# SCK_DATA_BOARD_2_0_REV_03.net
KiCad netlist of a schematic drawn in EAGLE
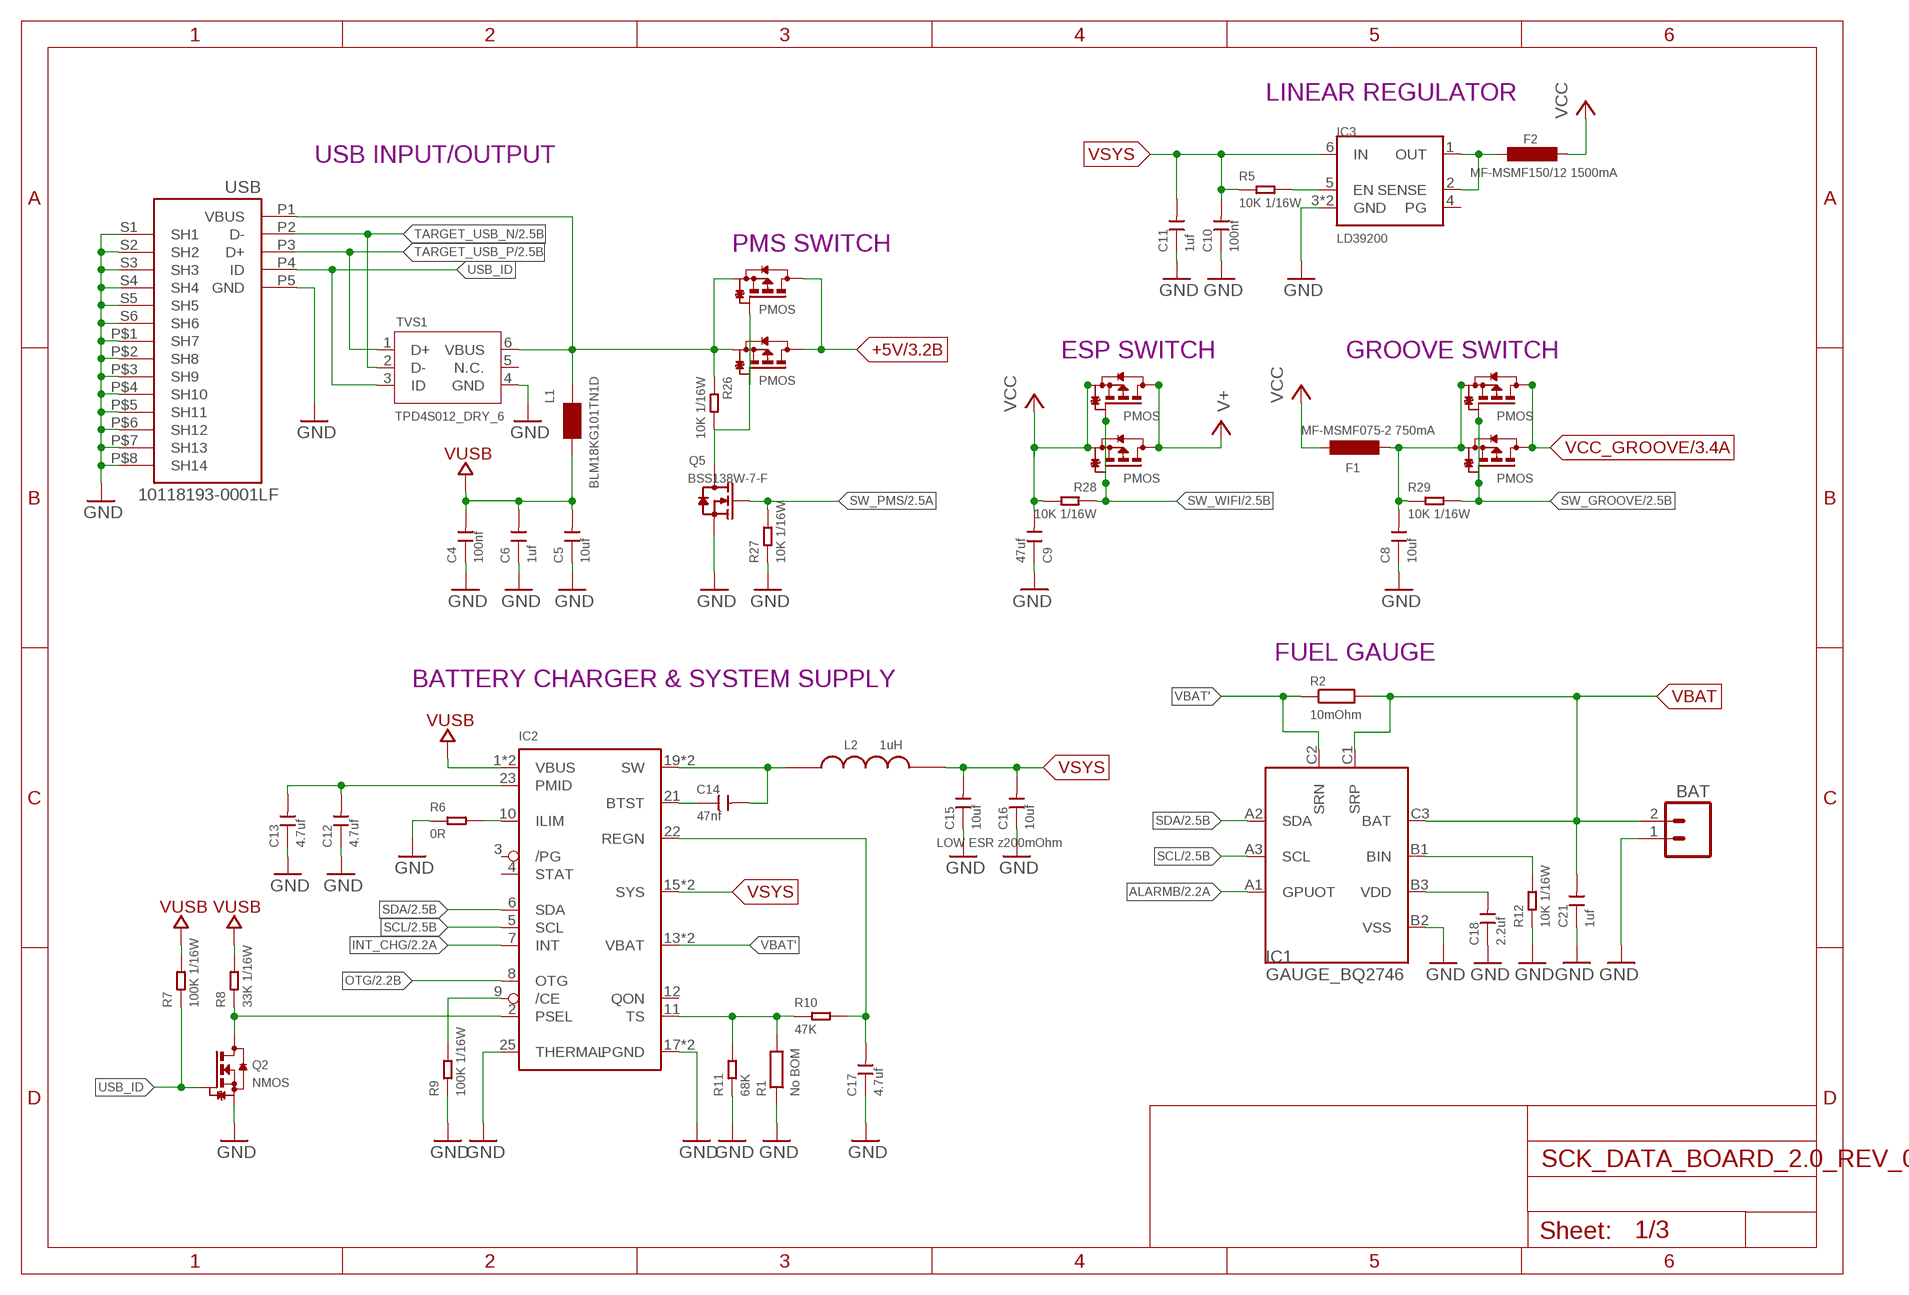
[diagram p0: schematic, sheet 1]
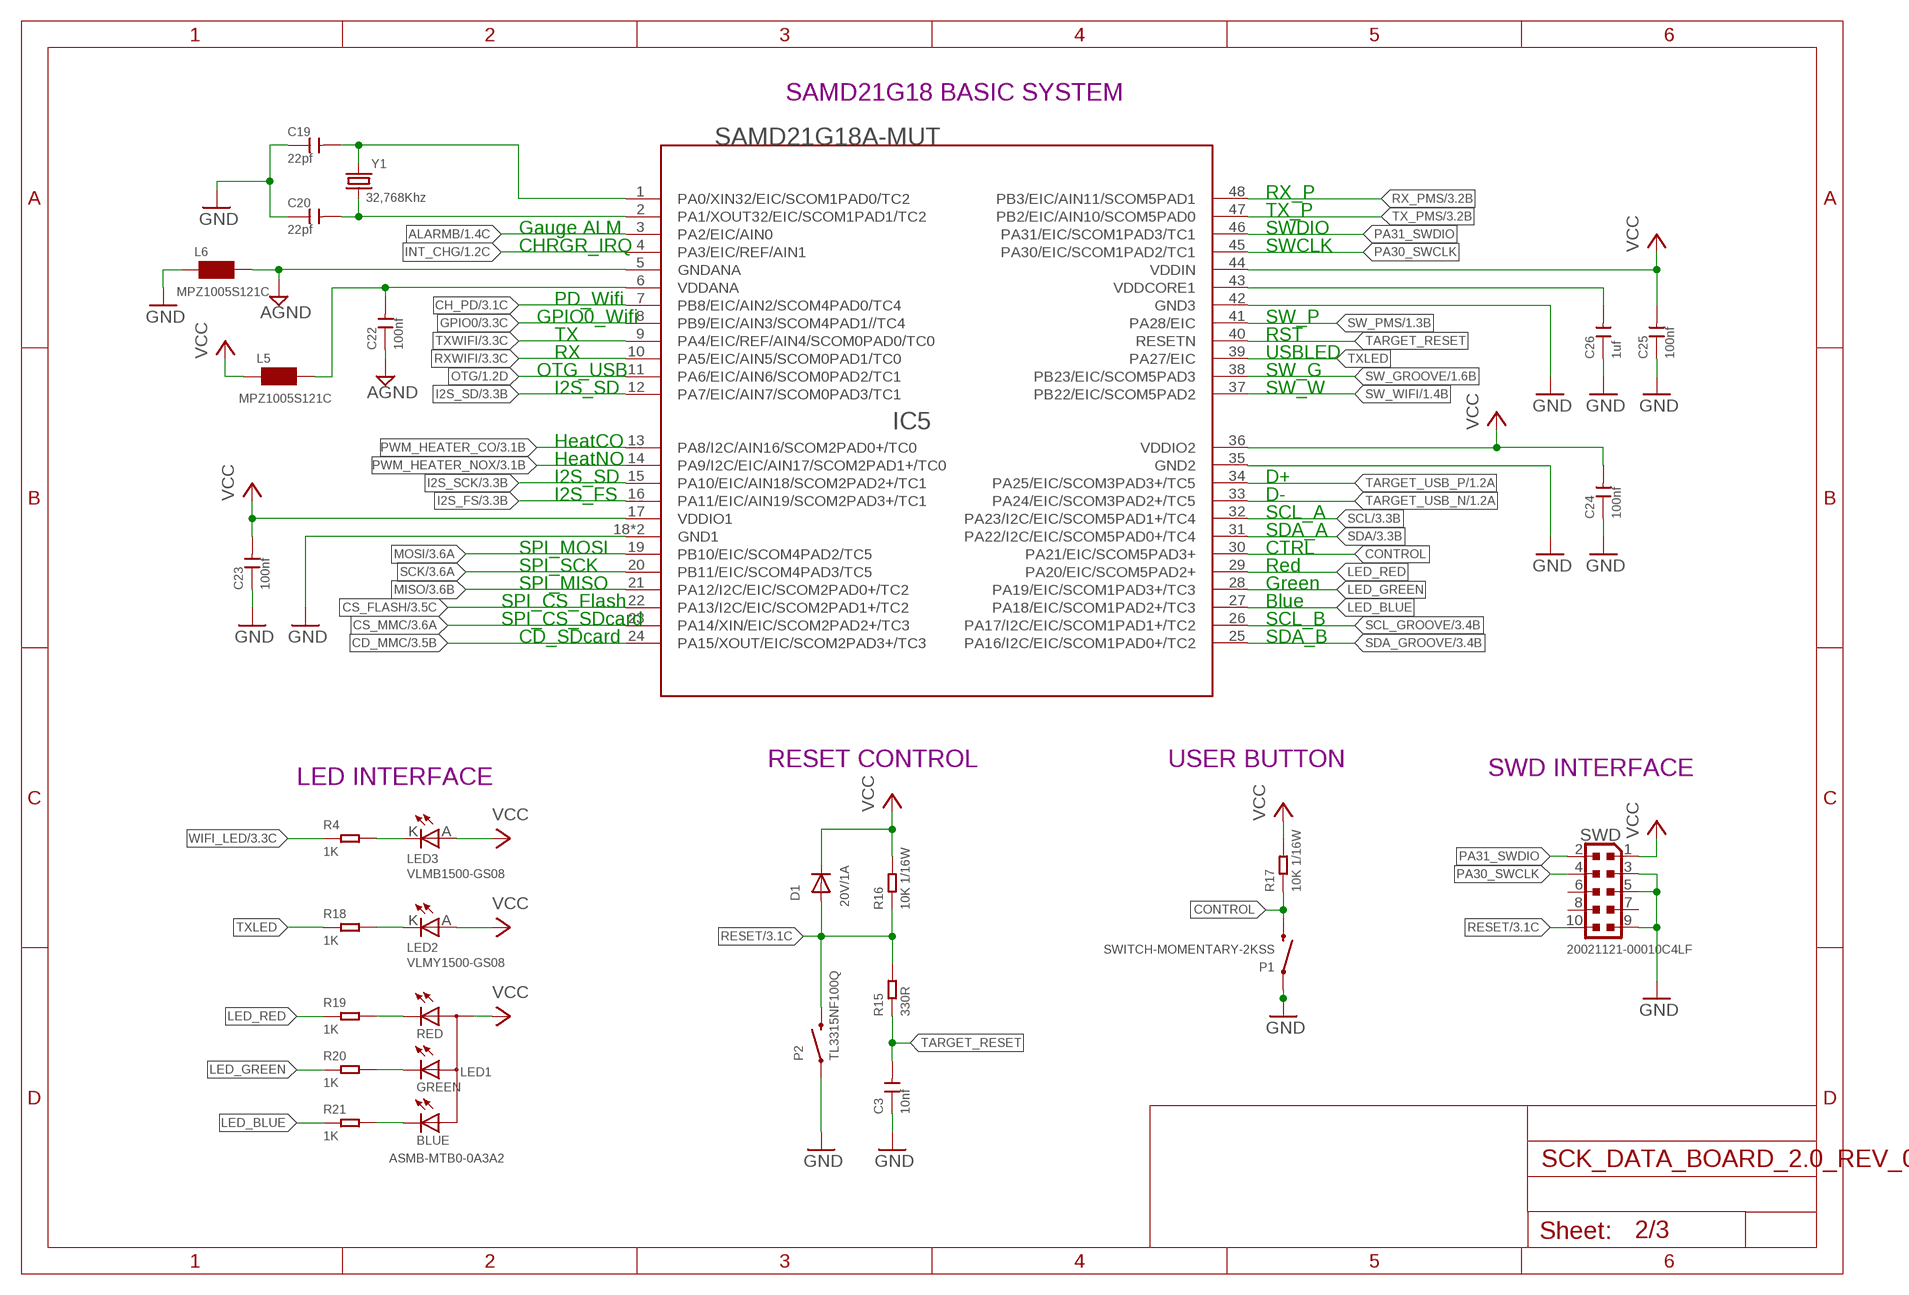
[diagram p1: schematic, sheet 2]
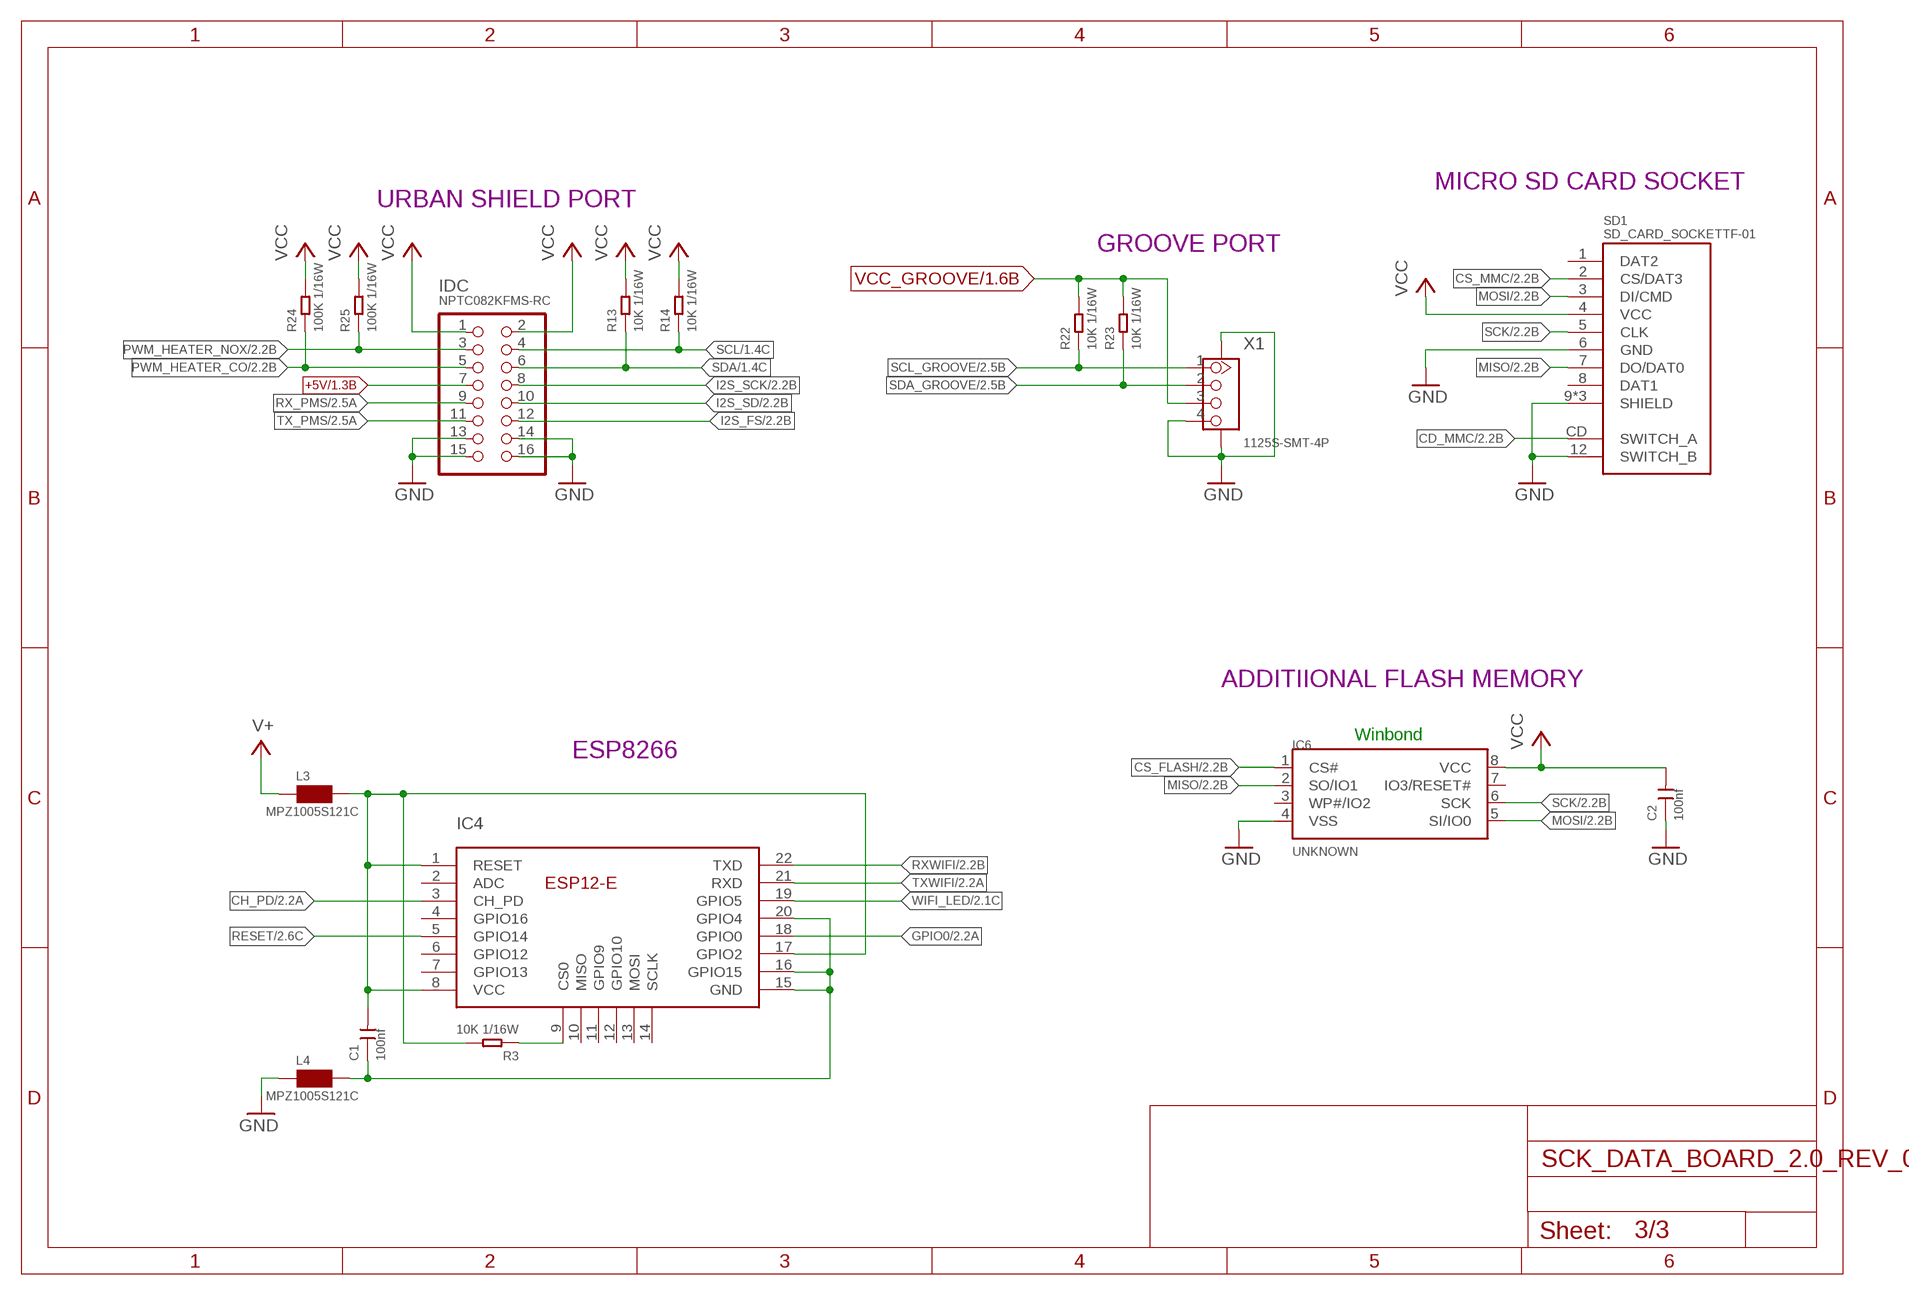
[diagram p2: schematic, sheet 3]

(export (version "E")
  (design (tool "Eeschema 10.0.6"))
  (components
    (comp (ref "BAT")
      (value "M02-JST-2MM-SMT")
      (footprint "eagle-import:S2B-PH")
      (libsource (lib "eagle-import") (part "M02-JST-2MM-SMT"))
    )
    (comp (ref "C4")
      (value "100nf")
      (footprint "eagle-import:C0805")
      (fields (field (name "MPN") "CC0805KRX7R9BB104"))
      (libsource (lib "eagle-import") (part "CERAMIC-100NF-50V-10%-X7R(0805)"))
    )
    (comp (ref "C5")
      (value "10uf")
      (footprint "eagle-import:C1206")
      (fields (field (name "MPN") "CC1206KKX5R8BB106"))
      (libsource (lib "eagle-import") (part "CERAMIC-10UF-25V-10%-X5R(1206)"))
    )
    (comp (ref "C6")
      (value "1uf")
      (footprint "eagle-import:C0805")
      (fields (field (name "MPN") "CC0805KKX7R8BB105"))
      (libsource (lib "eagle-import") (part "CERAMIC-1UF-25V-10%-X7R(0805)"))
    )
    (comp (ref "C8")
      (value "10uf")
      (footprint "eagle-import:C1206")
      (fields (field (name "MPN") "CC1206KKX5R8BB106"))
      (libsource (lib "eagle-import") (part "CERAMIC-10UF-25V-10%-X5R(1206)"))
    )
    (comp (ref "C9")
      (value "47uf")
      (footprint "eagle-import:C1210")
      (fields (field (name "MPN") "GRM32ER71A476ME15L"))
      (libsource (lib "eagle-import") (part "CERAMIC-47UF-10V-20%-X7R(1210)"))
    )
    (comp (ref "C10")
      (value "100nf")
      (footprint "eagle-import:C0603")
      (fields (field (name "MPN") "CC0603KRX7R9BB104"))
      (libsource (lib "eagle-import") (part "CERAMIC-100NF-50V-10%-X7R(0603)"))
    )
    (comp (ref "C11")
      (value "1uf")
      (footprint "eagle-import:C0805")
      (fields (field (name "MPN") "CC0805KKX7R8BB105"))
      (libsource (lib "eagle-import") (part "CERAMIC-1UF-25V-10%-X7R(0805)"))
    )
    (comp (ref "C12")
      (value "4.7uf")
      (footprint "eagle-import:C0603")
      (fields (field (name "MPN") "CC0603KRX5R6BB475"))
      (libsource (lib "eagle-import") (part "CERAMIC-4.7UF-10V-10%-X5R(0603)"))
    )
    (comp (ref "C13")
      (value "4.7uf")
      (footprint "eagle-import:C0603")
      (fields (field (name "MPN") "CC0603KRX5R6BB475"))
      (libsource (lib "eagle-import") (part "CERAMIC-4.7UF-10V-10%-X5R(0603)"))
    )
    (comp (ref "C14")
      (value "47nf")
      (footprint "eagle-import:C0402")
      (fields (field (name "MPN") "CC0402KRX7R8BB473"))
      (libsource (lib "eagle-import") (part "CERAMIC-47NF-25V-10%-X7R(0402)"))
    )
    (comp (ref "C15")
      (value "10uf")
      (footprint "eagle-import:C0603")
      (fields (field (name "MPN") "CC0603KRX5R6BB106"))
      (libsource (lib "eagle-import") (part "CERAMIC-10UF-10V-10%-X5R(0603)"))
    )
    (comp (ref "C16")
      (value "10uf")
      (footprint "eagle-import:C0603")
      (fields (field (name "MPN") "CC0603KRX5R6BB106"))
      (libsource (lib "eagle-import") (part "CERAMIC-10UF-10V-10%-X5R(0603)"))
    )
    (comp (ref "C17")
      (value "4.7uf")
      (footprint "eagle-import:C0805")
      (fields (field (name "MPN") "CC0805KKX5R8BB475"))
      (libsource (lib "eagle-import") (part "CERAMIC-4.7UF-25V-10%-X5R(0805)"))
    )
    (comp (ref "C18")
      (value "2.2uf")
      (footprint "eagle-import:C0603")
      (fields (field (name "MPN") "CC0603KRX7R6BB225"))
      (libsource (lib "eagle-import") (part "CERAMIC-2.2UF-10V-10%-X7R(0603)"))
    )
    (comp (ref "C21")
      (value "1uf")
      (footprint "eagle-import:C0805")
      (fields (field (name "MPN") "CC0805KKX7R8BB105"))
      (libsource (lib "eagle-import") (part "CERAMIC-1UF-25V-10%-X7R(0805)"))
    )
    (comp (ref "F1")
      (value "MF-MSMF075-2 750mA")
      (footprint "eagle-import:L1812")
      (libsource (lib "eagle-import") (part "L-EUL1812"))
    )
    (comp (ref "F2")
      (value "MF-MSMF150/12 1500mA")
      (footprint "eagle-import:L1812")
      (libsource (lib "eagle-import") (part "L-EUL1812"))
    )
    (comp (ref "IC1")
      (value "GAUGE_BQ2746")
      (footprint "eagle-import:BGA-9")
      (libsource (lib "eagle-import") (part "GAUGE_BQ2746"))
    )
    (comp (ref "IC2")
      (value "BQ24259_VQFN(24)")
      (footprint "eagle-import:24-PIN_VQFN_THPAD")
      (libsource (lib "eagle-import") (part "BQ24259_VQFN(24)"))
    )
    (comp (ref "IC3")
      (value "LD39200")
      (footprint "eagle-import:DFN6_3X3MM")
      (libsource (lib "eagle-import") (part "LD39200"))
    )
    (comp (ref "L1")
      (value "BLM18KG101TN1D")
      (footprint "eagle-import:WUERTH-ELEKTRONIK_0603")
      (libsource (lib "eagle-import") (part "WUERTH-ELEKTRONIK_WE-CBF_0603"))
    )
    (comp (ref "L2")
      (value "1uH")
      (footprint "eagle-import:HANGAR_C1210")
      (libsource (lib "eagle-import") (part "LQH32PN1R0NNCL"))
    )
    (comp (ref "Q1")
      (value "PMOS")
      (footprint "eagle-import:HANGAR_POWERPAKSC70-6L")
      (libsource (lib "eagle-import") (part "MOSFETP_BOTH"))
    )
    (comp (ref "Q2")
      (value "NMOS")
      (footprint "eagle-import:NMOS_UMT3")
      (libsource (lib "eagle-import") (part "NMOS_RJU003N03FRAT106"))
    )
    (comp (ref "Q3")
      (value "PMOS")
      (footprint "eagle-import:HANGAR_POWERPAKSC70-6L")
      (libsource (lib "eagle-import") (part "MOSFETP_BOTH"))
    )
    (comp (ref "Q4")
      (value "PMOS")
      (footprint "eagle-import:HANGAR_POWERPAKSC70-6L")
      (libsource (lib "eagle-import") (part "MOSFETP_BOTH"))
    )
    (comp (ref "Q5")
      (value "BSS138W-7-F")
      (footprint "eagle-import:SOT-23")
      (libsource (lib "eagle-import") (part "SMD-MOSFET-N-CH-50V-200MA-BSS138W-7-F(SOT-23)"))
    )
    (comp (ref "R1")
      (value "No BOM")
      (footprint "eagle-import:HANGAR_R0402")
      (libsource (lib "eagle-import") (part "HANGAR_R-EU_R0402"))
    )
    (comp (ref "R2")
      (value "10mOhm")
      (footprint "eagle-import:HANGAR_R0603")
      (libsource (lib "eagle-import") (part "SCK_URBAN_SHIELD_v1.6_HANGAR_R-EU_R0603"))
    )
    (comp (ref "R5")
      (value "10K 1/16W")
      (footprint "eagle-import:R0402")
      (fields (field (name "MPN") "RC0402FR-0710KL"))
      (libsource (lib "eagle-import") (part "SMD-RES-10K-1%-1/16W(0402)"))
    )
    (comp (ref "R6")
      (value "0R")
      (footprint "eagle-import:R0402")
      (fields (field (name "MPN") "RC0402JR-070RL"))
      (libsource (lib "eagle-import") (part "SMD-RES-0R-5%-1/16W(0402)"))
    )
    (comp (ref "R7")
      (value "100K 1/16W")
      (footprint "eagle-import:R0402")
      (fields (field (name "MPN") "RC0402JR-07100KL"))
      (libsource (lib "eagle-import") (part "SMD-RES-100K-5%-1/16W(0402)"))
    )
    (comp (ref "R8")
      (value "33K 1/16W")
      (footprint "eagle-import:R0402")
      (fields (field (name "MPN") "RC0402FR-0733KL"))
      (libsource (lib "eagle-import") (part "SMD-RES-33K-1%-1/16W(0402)"))
    )
    (comp (ref "R9")
      (value "100K 1/16W")
      (footprint "eagle-import:R0402")
      (fields (field (name "MPN") "RC0402JR-07100KL"))
      (libsource (lib "eagle-import") (part "SMD-RES-100K-5%-1/16W(0402)"))
    )
    (comp (ref "R10")
      (value "47K")
      (footprint "eagle-import:R0402")
      (fields (field (name "MPN") "RC0402JR-0747KL"))
      (libsource (lib "eagle-import") (part "SMD-RES-47K-5%-1/16W(0402)"))
    )
    (comp (ref "R11")
      (value "68K")
      (footprint "eagle-import:R0402")
      (fields (field (name "MPN") "RC0402JR-0768KL"))
      (libsource (lib "eagle-import") (part "SMD-RES-68K-50V-5%(0402)"))
    )
    (comp (ref "R12")
      (value "10K 1/16W")
      (footprint "eagle-import:R0402")
      (fields (field (name "MPN") "RC0402FR-0710KL"))
      (libsource (lib "eagle-import") (part "SMD-RES-10K-1%-1/16W(0402)"))
    )
    (comp (ref "R26")
      (value "10K 1/16W")
      (footprint "eagle-import:R0402")
      (fields (field (name "MPN") "RC0402FR-0710KL"))
      (libsource (lib "eagle-import") (part "Seeed-Resistor_SMD-RES-10K-1%-1/16W(0402)"))
    )
    (comp (ref "R27")
      (value "10K 1/16W")
      (footprint "eagle-import:R0402")
      (fields (field (name "MPN") "RC0402FR-0710KL"))
      (libsource (lib "eagle-import") (part "Seeed-Resistor_SMD-RES-10K-1%-1/16W(0402)"))
    )
    (comp (ref "R28")
      (value "10K 1/16W")
      (footprint "eagle-import:R0402")
      (fields (field (name "MPN") "RC0402FR-0710KL"))
      (libsource (lib "eagle-import") (part "Seeed-Resistor_SMD-RES-10K-1%-1/16W(0402)"))
    )
    (comp (ref "R29")
      (value "10K 1/16W")
      (footprint "eagle-import:R0402")
      (fields (field (name "MPN") "RC0402FR-0710KL"))
      (libsource (lib "eagle-import") (part "Seeed-Resistor_SMD-RES-10K-1%-1/16W(0402)"))
    )
    (comp (ref "TVS1")
      (value "TPD4S012_DRY_6")
      (footprint "eagle-import:DRY6")
      (libsource (lib "eagle-import") (part "TPD4S012_DRY_6"))
    )
    (comp (ref "USB")
      (value "10118193-0001LF")
      (footprint "eagle-import:HANGAR_CON2_USB_MICRO_B_AT")
      (libsource (lib "eagle-import") (part "HANGAR_MYCON2_USB-MINI-B"))
    )
    (comp (ref "C1")
      (value "100nf")
      (footprint "eagle-import:C0402")
      (fields (field (name "MPN") "CC0402KRX7R8BB104"))
      (libsource (lib "eagle-import") (part "CERAMIC-100NF-25V-10%-X7R(0402)"))
    )
    (comp (ref "C2")
      (value "100nf")
      (footprint "eagle-import:C0402")
      (fields (field (name "MPN") "CC0402KRX7R8BB104"))
      (libsource (lib "eagle-import") (part "CERAMIC-100NF-25V-10%-X7R(0402)"))
    )
    (comp (ref "IC4")
      (value "HANGAR_ESP-12-E")
      (footprint "eagle-import:HANGAR_ESP12-E")
      (libsource (lib "eagle-import") (part "HANGAR_ESP-12-E"))
    )
    (comp (ref "IC6")
      (value "UNKNOWN")
      (footprint "eagle-import:SOIC_8-208MILS")
      (libsource (lib "eagle-import") (part "FLASH_S25FL064L"))
    )
    (comp (ref "IDC")
      (value "NPTC082KFMS-RC")
      (footprint "eagle-import:2X08SMD_FEMALE")
      (libsource (lib "eagle-import") (part "PINHD-2X8/SMD"))
    )
    (comp (ref "L3")
      (value "MPZ1005S121C")
      (footprint "eagle-import:0402")
      (libsource (lib "eagle-import") (part "WE-CBF_0402"))
    )
    (comp (ref "L4")
      (value "MPZ1005S121C")
      (footprint "eagle-import:0402")
      (libsource (lib "eagle-import") (part "WE-CBF_0402"))
    )
    (comp (ref "R3")
      (value "10K 1/16W")
      (footprint "eagle-import:R0402")
      (fields (field (name "MPN") "RC0402FR-0710KL"))
      (libsource (lib "eagle-import") (part "SMD-RES-10K-1%-1/16W(0402)"))
    )
    (comp (ref "R13")
      (value "10K 1/16W")
      (footprint "eagle-import:R0402")
      (fields (field (name "MPN") "RC0402FR-0710KL"))
      (libsource (lib "eagle-import") (part "SMD-RES-10K-1%-1/16W(0402)"))
    )
    (comp (ref "R14")
      (value "10K 1/16W")
      (footprint "eagle-import:R0402")
      (fields (field (name "MPN") "RC0402FR-0710KL"))
      (libsource (lib "eagle-import") (part "SMD-RES-10K-1%-1/16W(0402)"))
    )
    (comp (ref "R22")
      (value "10K 1/16W")
      (footprint "eagle-import:R0402")
      (fields (field (name "MPN") "RC0402FR-0710KL"))
      (libsource (lib "eagle-import") (part "SMD-RES-10K-1%-1/16W(0402)"))
    )
    (comp (ref "R23")
      (value "10K 1/16W")
      (footprint "eagle-import:R0402")
      (fields (field (name "MPN") "RC0402FR-0710KL"))
      (libsource (lib "eagle-import") (part "SMD-RES-10K-1%-1/16W(0402)"))
    )
    (comp (ref "R24")
      (value "100K 1/16W")
      (footprint "eagle-import:R0402")
      (fields (field (name "MPN") "RC0402JR-07100KL"))
      (libsource (lib "eagle-import") (part "SMD-RES-100K-5%-1/16W(0402)"))
    )
    (comp (ref "R25")
      (value "100K 1/16W")
      (footprint "eagle-import:R0402")
      (fields (field (name "MPN") "RC0402JR-07100KL"))
      (libsource (lib "eagle-import") (part "SMD-RES-100K-5%-1/16W(0402)"))
    )
    (comp (ref "SD1")
      (value "SD_CARD_SOCKETTF-01")
      (footprint "eagle-import:TF-01")
      (libsource (lib "eagle-import") (part "SD_CARD_SOCKETTF-01"))
    )
    (comp (ref "X1")
      (value "1125S-SMT-4P")
      (footprint "eagle-import:HW4-SMD-2.0")
      (libsource (lib "eagle-import") (part "GROVE-CONNECTOR-SMD'DD'"))
    )
    (comp (ref "C3")
      (value "10nf")
      (footprint "eagle-import:C0402")
      (fields (field (name "MPN") "CC0402KRX7R9BB103"))
      (libsource (lib "eagle-import") (part "CERAMIC-10NF-50V-10%-X7R(0402)"))
    )
    (comp (ref "C19")
      (value "22pf")
      (footprint "eagle-import:C0402")
      (fields (field (name "MPN") "CC0402JRNPO9BN220"))
      (libsource (lib "eagle-import") (part "CERAMIC-22PF-50V-5%-NPO(0402)"))
    )
    (comp (ref "C20")
      (value "22pf")
      (footprint "eagle-import:C0402")
      (fields (field (name "MPN") "CC0402JRNPO9BN220"))
      (libsource (lib "eagle-import") (part "CERAMIC-22PF-50V-5%-NPO(0402)"))
    )
    (comp (ref "C22")
      (value "100nf")
      (footprint "eagle-import:C0402")
      (fields (field (name "MPN") "CC0402KRX7R8BB104"))
      (libsource (lib "eagle-import") (part "CERAMIC-100NF-25V-10%-X7R(0402)"))
    )
    (comp (ref "C23")
      (value "100nf")
      (footprint "eagle-import:C0402")
      (fields (field (name "MPN") "CC0402KRX7R8BB104"))
      (libsource (lib "eagle-import") (part "CERAMIC-100NF-25V-10%-X7R(0402)"))
    )
    (comp (ref "C24")
      (value "100nf")
      (footprint "eagle-import:C0402")
      (fields (field (name "MPN") "CC0402KRX7R8BB104"))
      (libsource (lib "eagle-import") (part "CERAMIC-100NF-25V-10%-X7R(0402)"))
    )
    (comp (ref "C25")
      (value "100nf")
      (footprint "eagle-import:C0402")
      (fields (field (name "MPN") "CC0402KRX7R8BB104"))
      (libsource (lib "eagle-import") (part "CERAMIC-100NF-25V-10%-X7R(0402)"))
    )
    (comp (ref "C26")
      (value "1uf")
      (footprint "eagle-import:C0402")
      (fields (field (name "MPN") "CC0402KRX5R6BB105"))
      (libsource (lib "eagle-import") (part "CERAMIC-1UF-10V-10%-X5R(0402)"))
    )
    (comp (ref "D1")
      (value "20V/1A")
      (footprint "eagle-import:SOD323-R")
      (libsource (lib "eagle-import") (part "DIODE-SOD323-R"))
    )
    (comp (ref "IC5")
      (value "SAMD21G18A-MUT")
      (footprint "eagle-import:HANGAR_QFN48-7X7")
      (libsource (lib "eagle-import") (part "HANGAR_SAMD21G18A-MUT"))
    )
    (comp (ref "L5")
      (value "MPZ1005S121C")
      (footprint "eagle-import:0402")
      (libsource (lib "eagle-import") (part "WE-CBF_0402"))
    )
    (comp (ref "L6")
      (value "MPZ1005S121C")
      (footprint "eagle-import:0402")
      (libsource (lib "eagle-import") (part "WE-CBF_0402"))
    )
    (comp (ref "LED1")
      (value "ASMB-MTB0-0A3A2")
      (footprint "eagle-import:P-LCC-4")
      (libsource (lib "eagle-import") (part "LED_RGB_CAASMB-MTB0-0A3A2"))
    )
    (comp (ref "LED2")
      (value "VLMY1500-GS08")
      (footprint "eagle-import:DIODE_0402_R")
      (libsource (lib "eagle-import") (part "LED_SMALL"))
    )
    (comp (ref "LED3")
      (value "VLMB1500-GS08")
      (footprint "eagle-import:DIODE_0402_R")
      (libsource (lib "eagle-import") (part "LED_SMALL"))
    )
    (comp (ref "P1")
      (value "SWITCH-MOMENTARY-2KSS")
      (footprint "eagle-import:KSS241G")
      (libsource (lib "eagle-import") (part "SWITCH-MOMENTARY-2KSS"))
    )
    (comp (ref "P2")
      (value "TL3315NF100Q")
      (footprint "eagle-import:SPST_SMD_SWITCH")
      (libsource (lib "eagle-import") (part "RESET_BTN_TL3315NF100Q"))
    )
    (comp (ref "R4")
      (value "1K")
      (footprint "eagle-import:R0402")
      (fields (field (name "MPN") "RC0402JR-071KL"))
      (libsource (lib "eagle-import") (part "SMD-RES-1K-5%-1/16W(0402)"))
    )
    (comp (ref "R15")
      (value "330R")
      (footprint "eagle-import:R0402")
      (fields (field (name "MPN") "RC0402FR-07330RL"))
      (libsource (lib "eagle-import") (part "SMD-RES-330R-1%-1/16W(0402)"))
    )
    (comp (ref "R16")
      (value "10K 1/16W")
      (footprint "eagle-import:R0402")
      (fields (field (name "MPN") "RC0402FR-0710KL"))
      (libsource (lib "eagle-import") (part "SMD-RES-10K-1%-1/16W(0402)"))
    )
    (comp (ref "R17")
      (value "10K 1/16W")
      (footprint "eagle-import:R0402")
      (fields (field (name "MPN") "RC0402FR-0710KL"))
      (libsource (lib "eagle-import") (part "SMD-RES-10K-1%-1/16W(0402)"))
    )
    (comp (ref "R18")
      (value "1K")
      (footprint "eagle-import:R0402")
      (fields (field (name "MPN") "RC0402JR-071KL"))
      (libsource (lib "eagle-import") (part "SMD-RES-1K-5%-1/16W(0402)"))
    )
    (comp (ref "R19")
      (value "1K")
      (footprint "eagle-import:R0402")
      (fields (field (name "MPN") "RC0402JR-071KL"))
      (libsource (lib "eagle-import") (part "SMD-RES-1K-5%-1/16W(0402)"))
    )
    (comp (ref "R20")
      (value "1K")
      (footprint "eagle-import:R0402")
      (fields (field (name "MPN") "RC0402JR-071KL"))
      (libsource (lib "eagle-import") (part "SMD-RES-1K-5%-1/16W(0402)"))
    )
    (comp (ref "R21")
      (value "1K")
      (footprint "eagle-import:R0402")
      (fields (field (name "MPN") "RC0402JR-071KL"))
      (libsource (lib "eagle-import") (part "SMD-RES-1K-5%-1/16W(0402)"))
    )
    (comp (ref "SWD")
      (value "20021121-00010C4LF")
      (footprint "eagle-import:2X05_SMD_1.27MM")
      (libsource (lib "eagle-import") (part "PINHEAD_PINHD-2X5SMD"))
    )
    (comp (ref "Y1")
      (value "32,768Khz")
      (footprint "eagle-import:RESONATOR_EPSON_FC_145")
      (fields (field (name "PART_NUMBER") "ABS07-32.768KHZ-T"))
      (libsource (lib "eagle-import") (part "0213_ABS07-32.768KHZ-T"))
    )
  )
  (nets
    (net (code "1") (name "+5V") (class "Default")
      (node (ref "IDC") (pin "7") (pinfunction "7_7") (pintype "passive"))
      (node (ref "Q1") (pin "3") (pinfunction "D_3") (pintype "passive"))
      (node (ref "Q1") (pin "6") (pinfunction "D_6") (pintype "passive"))
      (node (ref "Q1") (pin "TP1") (pinfunction "D_TP1") (pintype "passive"))
      (node (ref "Q1") (pin "TP2") (pinfunction "D_TP2") (pintype "passive"))
    )
    (net (code "2") (name "AGND") (class "Default")
      (node (ref "C22") (pin "1") (pinfunction "1_1") (pintype "passive"))
      (node (ref "IC5") (pin "5") (pinfunction "GNDANA_5") (pintype "power_in"))
      (node (ref "L6") (pin "2") (pinfunction "2_2") (pintype "passive"))
    )
    (net (code "3") (name "ALARMB") (class "Default")
      (node (ref "IC1") (pin "A1") (pinfunction "GPUOT_A1") (pintype "bidirectional"))
      (node (ref "IC5") (pin "3") (pinfunction "PA2/EIC/AIN0_3") (pintype "bidirectional"))
    )
    (net (code "4") (name "CD_MMC") (class "Default")
      (node (ref "IC5") (pin "24") (pinfunction "PA15/XOUT/EIC/SCOM2PAD3+/TC3_24") (pintype "bidirectional"))
      (node (ref "SD1") (pin "CD") (pinfunction "SWITCH_A_CD") (pintype "bidirectional"))
    )
    (net (code "5") (name "CH_PD") (class "Default")
      (node (ref "IC4") (pin "3") (pinfunction "CH_PD_3") (pintype "input"))
      (node (ref "IC5") (pin "7") (pinfunction "PB8/EIC/AIN2/SCOM4PAD0/TC4_7") (pintype "bidirectional"))
    )
    (net (code "6") (name "CONTROL") (class "Default")
      (node (ref "IC5") (pin "30") (pinfunction "PA21/EIC/SCOM5PAD3+_30") (pintype "bidirectional"))
      (node (ref "P1") (pin "2") (pinfunction "2_2") (pintype "passive"))
      (node (ref "R17") (pin "1") (pinfunction "1_1") (pintype "passive"))
    )
    (net (code "7") (name "CS_FLASH") (class "Default")
      (node (ref "IC5") (pin "22") (pinfunction "PA13/I2C/EIC/SCOM2PAD1+/TC2_22") (pintype "bidirectional"))
      (node (ref "IC6") (pin "1") (pinfunction "CS#_1") (pintype "bidirectional"))
    )
    (net (code "8") (name "CS_MMC") (class "Default")
      (node (ref "IC5") (pin "23") (pinfunction "PA14/XIN/EIC/SCOM2PAD2+/TC3_23") (pintype "bidirectional"))
      (node (ref "SD1") (pin "2") (pinfunction "CS/DAT3_2") (pintype "bidirectional"))
    )
    (net (code "9") (name "GND") (class "Default")
      (node (ref "BAT") (pin "1") (pinfunction "1_1") (pintype "passive"))
      (node (ref "C10") (pin "1") (pinfunction "1_1") (pintype "passive"))
      (node (ref "C11") (pin "1") (pinfunction "1_1") (pintype "passive"))
      (node (ref "C12") (pin "1") (pinfunction "1_1") (pintype "passive"))
      (node (ref "C13") (pin "1") (pinfunction "1_1") (pintype "passive"))
      (node (ref "C15") (pin "1") (pinfunction "1_1") (pintype "passive"))
      (node (ref "C16") (pin "1") (pinfunction "1_1") (pintype "passive"))
      (node (ref "C17") (pin "1") (pinfunction "1_1") (pintype "passive"))
      (node (ref "C18") (pin "1") (pinfunction "1_1") (pintype "passive"))
      (node (ref "C19") (pin "1") (pinfunction "1_1") (pintype "passive"))
      (node (ref "C2") (pin "1") (pinfunction "1_1") (pintype "passive"))
      (node (ref "C20") (pin "1") (pinfunction "1_1") (pintype "passive"))
      (node (ref "C21") (pin "1") (pinfunction "1_1") (pintype "passive"))
      (node (ref "C23") (pin "1") (pinfunction "1_1") (pintype "passive"))
      (node (ref "C24") (pin "1") (pinfunction "1_1") (pintype "passive"))
      (node (ref "C25") (pin "1") (pinfunction "1_1") (pintype "passive"))
      (node (ref "C26") (pin "1") (pinfunction "1_1") (pintype "passive"))
      (node (ref "C3") (pin "1") (pinfunction "1_1") (pintype "passive"))
      (node (ref "C4") (pin "1") (pinfunction "1_1") (pintype "passive"))
      (node (ref "C5") (pin "1") (pinfunction "1_1") (pintype "passive"))
      (node (ref "C6") (pin "1") (pinfunction "1_1") (pintype "passive"))
      (node (ref "C8") (pin "1") (pinfunction "1_1") (pintype "passive"))
      (node (ref "C9") (pin "1") (pinfunction "1_1") (pintype "passive"))
      (node (ref "IC1") (pin "B2") (pinfunction "VSS_B2") (pintype "bidirectional"))
      (node (ref "IC2") (pin "17") (pinfunction "PGND_17") (pintype "bidirectional"))
      (node (ref "IC2") (pin "18") (pinfunction "PGND_18") (pintype "bidirectional"))
      (node (ref "IC2") (pin "25") (pinfunction "THERMAL_25") (pintype "bidirectional"))
      (node (ref "IC3") (pin "3") (pinfunction "GND_3") (pintype "bidirectional"))
      (node (ref "IC3") (pin "7") (pinfunction "GND_7") (pintype "bidirectional"))
      (node (ref "IC5") (pin "18") (pinfunction "GND1_18") (pintype "power_in"))
      (node (ref "IC5") (pin "35") (pinfunction "GND2_35") (pintype "power_in"))
      (node (ref "IC5") (pin "42") (pinfunction "GND3_42") (pintype "power_in"))
      (node (ref "IC5") (pin "TP") (pinfunction "GND1_TP") (pintype "power_in"))
      (node (ref "IC6") (pin "4") (pinfunction "VSS_4") (pintype "bidirectional"))
      (node (ref "IDC") (pin "13") (pinfunction "13_13") (pintype "passive"))
      (node (ref "IDC") (pin "14") (pinfunction "14_14") (pintype "passive"))
      (node (ref "IDC") (pin "15") (pinfunction "15_15") (pintype "passive"))
      (node (ref "IDC") (pin "16") (pinfunction "16_16") (pintype "passive"))
      (node (ref "L4") (pin "2") (pinfunction "2_2") (pintype "passive"))
      (node (ref "L6") (pin "1") (pinfunction "1_1") (pintype "passive"))
      (node (ref "P1") (pin "1") (pinfunction "1_1") (pintype "passive"))
      (node (ref "P2") (pin "1") (pinfunction "1_1") (pintype "passive"))
      (node (ref "P2") (pin "2") (pinfunction "1_2") (pintype "passive"))
      (node (ref "Q2") (pin "1") (pinfunction "S_1") (pintype "passive"))
      (node (ref "Q5") (pin "2") (pinfunction "S_2") (pintype "passive"))
      (node (ref "R1") (pin "1") (pinfunction "1_1") (pintype "passive"))
      (node (ref "R11") (pin "1") (pinfunction "1_1") (pintype "passive"))
      (node (ref "R12") (pin "1") (pinfunction "1_1") (pintype "passive"))
      (node (ref "R27") (pin "1") (pinfunction "1_1") (pintype "passive"))
      (node (ref "R6") (pin "1") (pinfunction "1_1") (pintype "passive"))
      (node (ref "R9") (pin "1") (pinfunction "1_1") (pintype "passive"))
      (node (ref "SD1") (pin "10") (pinfunction "SHIELD_10") (pintype "bidirectional"))
      (node (ref "SD1") (pin "11") (pinfunction "SHIELD_11") (pintype "bidirectional"))
      (node (ref "SD1") (pin "12") (pinfunction "SWITCH_B_12") (pintype "bidirectional"))
      (node (ref "SD1") (pin "6") (pinfunction "GND_6") (pintype "bidirectional"))
      (node (ref "SD1") (pin "9") (pinfunction "SHIELD_9") (pintype "bidirectional"))
      (node (ref "SWD") (pin "3") (pinfunction "3_3") (pintype "passive"))
      (node (ref "SWD") (pin "5") (pinfunction "5_5") (pintype "passive"))
      (node (ref "SWD") (pin "9") (pinfunction "9_9") (pintype "passive"))
      (node (ref "TVS1") (pin "4") (pinfunction "GND_4") (pintype "passive"))
      (node (ref "USB") (pin "P$1") (pinfunction "SH7_P$1") (pintype "passive"))
      (node (ref "USB") (pin "P$2") (pinfunction "SH8_P$2") (pintype "passive"))
      (node (ref "USB") (pin "P$3") (pinfunction "SH9_P$3") (pintype "passive"))
      (node (ref "USB") (pin "P$4") (pinfunction "SH10_P$4") (pintype "passive"))
      (node (ref "USB") (pin "P$5") (pinfunction "SH11_P$5") (pintype "passive"))
      (node (ref "USB") (pin "P$6") (pinfunction "SH12_P$6") (pintype "passive"))
      (node (ref "USB") (pin "P$7") (pinfunction "SH13_P$7") (pintype "passive"))
      (node (ref "USB") (pin "P$8") (pinfunction "SH14_P$8") (pintype "passive"))
      (node (ref "USB") (pin "P5") (pinfunction "GND_P5") (pintype "passive"))
      (node (ref "USB") (pin "S1") (pinfunction "SH1_S1") (pintype "passive"))
      (node (ref "USB") (pin "S2") (pinfunction "SH2_S2") (pintype "passive"))
      (node (ref "USB") (pin "S3") (pinfunction "SH3_S3") (pintype "passive"))
      (node (ref "USB") (pin "S4") (pinfunction "SH4_S4") (pintype "passive"))
      (node (ref "USB") (pin "S5") (pinfunction "SH5_S5") (pintype "passive"))
      (node (ref "USB") (pin "S6") (pinfunction "SH6_S6") (pintype "passive"))
      (node (ref "X1") (pin "4") (pinfunction "4_4") (pintype "bidirectional"))
      (node (ref "X1") (pin "SS1") (pinfunction "SS1_SS1") (pintype "bidirectional"))
      (node (ref "X1") (pin "SS2") (pinfunction "SS2_SS2") (pintype "bidirectional"))
    )
    (net (code "10") (name "GPIO0") (class "Default")
      (node (ref "IC4") (pin "18") (pinfunction "GPIO0_18") (pintype "bidirectional"))
      (node (ref "IC5") (pin "8") (pinfunction "PB9/EIC/AIN3/SCOM4PAD1//TC4_8") (pintype "bidirectional"))
    )
    (net (code "11") (name "I2S_FS") (class "Default")
      (node (ref "IC5") (pin "16") (pinfunction "PA11/EIC/AIN19/SCOM2PAD3+/TC1_16") (pintype "bidirectional"))
      (node (ref "IDC") (pin "12") (pinfunction "12_12") (pintype "passive"))
    )
    (net (code "12") (name "I2S_SCK") (class "Default")
      (node (ref "IC5") (pin "15") (pinfunction "PA10/EIC/AIN18/SCOM2PAD2+/TC1_15") (pintype "bidirectional"))
      (node (ref "IDC") (pin "8") (pinfunction "8_8") (pintype "passive"))
    )
    (net (code "13") (name "I2S_SD") (class "Default")
      (node (ref "IC5") (pin "12") (pinfunction "PA7/EIC/AIN7/SCOM0PAD3/TC1_12") (pintype "bidirectional"))
      (node (ref "IDC") (pin "10") (pinfunction "10_10") (pintype "passive"))
    )
    (net (code "14") (name "INT_CHG") (class "Default")
      (node (ref "IC2") (pin "7") (pinfunction "INT_7") (pintype "bidirectional"))
      (node (ref "IC5") (pin "4") (pinfunction "PA3/EIC/REF/AIN1_4") (pintype "bidirectional"))
    )
    (net (code "15") (name "LED_BLUE") (class "Default")
      (node (ref "IC5") (pin "27") (pinfunction "PA18/EIC/SCOM1PAD2+/TC3_27") (pintype "bidirectional"))
      (node (ref "R21") (pin "1") (pinfunction "1_1") (pintype "passive"))
    )
    (net (code "16") (name "LED_GREEN") (class "Default")
      (node (ref "IC5") (pin "28") (pinfunction "PA19/EIC/SCOM1PAD3+/TC3_28") (pintype "bidirectional"))
      (node (ref "R20") (pin "1") (pinfunction "1_1") (pintype "passive"))
    )
    (net (code "17") (name "LED_RED") (class "Default")
      (node (ref "IC5") (pin "29") (pinfunction "PA20/EIC/SCOM5PAD2+_29") (pintype "bidirectional"))
      (node (ref "R19") (pin "1") (pinfunction "1_1") (pintype "passive"))
    )
    (net (code "18") (name "MISO") (class "Default")
      (node (ref "IC5") (pin "21") (pinfunction "PA12/I2C/EIC/SCOM2PAD0+/TC2_21") (pintype "bidirectional"))
      (node (ref "IC6") (pin "2") (pinfunction "SO/IO1_2") (pintype "bidirectional"))
      (node (ref "SD1") (pin "7") (pinfunction "DO/DAT0_7") (pintype "bidirectional"))
    )
    (net (code "19") (name "MOSI") (class "Default")
      (node (ref "IC5") (pin "19") (pinfunction "PB10/EIC/SCOM4PAD2/TC5_19") (pintype "bidirectional"))
      (node (ref "IC6") (pin "5") (pinfunction "SI/IO0_5") (pintype "bidirectional"))
      (node (ref "SD1") (pin "3") (pinfunction "DI/CMD_3") (pintype "bidirectional"))
    )
    (net (code "20") (name "Net-(C14-Pad2)") (class "Default")
      (node (ref "C14") (pin "2") (pinfunction "2_2") (pintype "passive"))
      (node (ref "IC2") (pin "19") (pinfunction "SW_19") (pintype "bidirectional"))
      (node (ref "IC2") (pin "20") (pinfunction "SW_20") (pintype "bidirectional"))
      (node (ref "L2") (pin "1") (pinfunction "1_1") (pintype "bidirectional"))
    )
    (net (code "21") (name "Net-(IC1-BIN)") (class "Default")
      (node (ref "IC1") (pin "B1") (pinfunction "BIN_B1") (pintype "bidirectional"))
      (node (ref "R12") (pin "2") (pinfunction "2_2") (pintype "passive"))
    )
    (net (code "22") (name "Net-(IC1-VDD)") (class "Default")
      (node (ref "C18") (pin "2") (pinfunction "2_2") (pintype "passive"))
      (node (ref "IC1") (pin "B3") (pinfunction "VDD_B3") (pintype "bidirectional"))
    )
    (net (code "23") (name "Net-(IC2-BTST)") (class "Default")
      (node (ref "C14") (pin "1") (pinfunction "1_1") (pintype "passive"))
      (node (ref "IC2") (pin "21") (pinfunction "BTST_21") (pintype "bidirectional"))
    )
    (net (code "24") (name "Net-(IC2-ILIM)") (class "Default")
      (node (ref "IC2") (pin "10") (pinfunction "ILIM_10") (pintype "bidirectional"))
      (node (ref "R6") (pin "2") (pinfunction "2_2") (pintype "passive"))
    )
    (net (code "25") (name "Net-(IC2-PMID)") (class "Default")
      (node (ref "C12") (pin "2") (pinfunction "2_2") (pintype "passive"))
      (node (ref "C13") (pin "2") (pinfunction "2_2") (pintype "passive"))
      (node (ref "IC2") (pin "23") (pinfunction "PMID_23") (pintype "bidirectional"))
    )
    (net (code "26") (name "Net-(IC2-PSEL)") (class "Default")
      (node (ref "IC2") (pin "2") (pinfunction "PSEL_2") (pintype "bidirectional"))
      (node (ref "Q2") (pin "3") (pinfunction "D_3") (pintype "passive"))
      (node (ref "R8") (pin "1") (pinfunction "1_1") (pintype "passive"))
    )
    (net (code "27") (name "Net-(IC2-REGN)") (class "Default")
      (node (ref "C17") (pin "2") (pinfunction "2_2") (pintype "passive"))
      (node (ref "IC2") (pin "22") (pinfunction "REGN_22") (pintype "bidirectional"))
      (node (ref "R10") (pin "2") (pinfunction "2_2") (pintype "passive"))
    )
    (net (code "28") (name "Net-(IC2-TS)") (class "Default")
      (node (ref "IC2") (pin "11") (pinfunction "TS_11") (pintype "bidirectional"))
      (node (ref "R1") (pin "2") (pinfunction "2_2") (pintype "passive"))
      (node (ref "R10") (pin "1") (pinfunction "1_1") (pintype "passive"))
      (node (ref "R11") (pin "2") (pinfunction "2_2") (pintype "passive"))
    )
    (net (code "29") (name "Net-(IC2-{slash}CE)") (class "Default")
      (node (ref "IC2") (pin "9") (pinfunction "/CE_9") (pintype "bidirectional"))
      (node (ref "R9") (pin "2") (pinfunction "2_2") (pintype "passive"))
    )
    (net (code "30") (name "Net-(IC3-EN)") (class "Default")
      (node (ref "IC3") (pin "5") (pinfunction "EN_5") (pintype "bidirectional"))
      (node (ref "R5") (pin "2") (pinfunction "2_2") (pintype "passive"))
    )
    (net (code "31") (name "Net-(IC3-OUT)") (class "Default")
      (node (ref "F2") (pin "2") (pinfunction "2_2") (pintype "passive"))
      (node (ref "IC3") (pin "1") (pinfunction "OUT_1") (pintype "bidirectional"))
      (node (ref "IC3") (pin "2") (pinfunction "SENSE_2") (pintype "bidirectional"))
    )
    (net (code "32") (name "Net-(IC4-CS0)") (class "Default")
      (node (ref "IC4") (pin "9") (pinfunction "CS0_9") (pintype "input"))
      (node (ref "R3") (pin "1") (pinfunction "1_1") (pintype "passive"))
    )
    (net (code "33") (name "Net-(IC4-GND)") (class "Default")
      (node (ref "C1") (pin "1") (pinfunction "1_1") (pintype "passive"))
      (node (ref "IC4") (pin "15") (pinfunction "GND_15") (pintype "power_in"))
      (node (ref "IC4") (pin "16") (pinfunction "GPIO15_16") (pintype "bidirectional"))
      (node (ref "IC4") (pin "20") (pinfunction "GPIO4_20") (pintype "bidirectional"))
      (node (ref "L4") (pin "1") (pinfunction "1_1") (pintype "passive"))
    )
    (net (code "34") (name "Net-(IC4-GPIO2)") (class "Default")
      (node (ref "C1") (pin "2") (pinfunction "2_2") (pintype "passive"))
      (node (ref "IC4") (pin "1") (pinfunction "RESET_1") (pintype "input"))
      (node (ref "IC4") (pin "17") (pinfunction "GPIO2_17") (pintype "bidirectional"))
      (node (ref "IC4") (pin "8") (pinfunction "VCC_8") (pintype "power_in"))
      (node (ref "L3") (pin "1") (pinfunction "1_1") (pintype "passive"))
      (node (ref "R3") (pin "2") (pinfunction "2_2") (pintype "passive"))
    )
    (net (code "35") (name "Net-(IC5-PA0{slash}XIN32{slash}EIC{slash}SCOM1PAD0{slash}TC2)") (class "Default")
      (node (ref "C19") (pin "2") (pinfunction "2_2") (pintype "passive"))
      (node (ref "IC5") (pin "1") (pinfunction "PA0/XIN32/EIC/SCOM1PAD0/TC2_1") (pintype "bidirectional"))
      (node (ref "Y1") (pin "P$2") (pinfunction "2_P$2") (pintype "bidirectional"))
    )
    (net (code "36") (name "Net-(IC5-PA1{slash}XOUT32{slash}EIC{slash}SCOM1PAD1{slash}TC2)") (class "Default")
      (node (ref "C20") (pin "2") (pinfunction "2_2") (pintype "passive"))
      (node (ref "IC5") (pin "2") (pinfunction "PA1/XOUT32/EIC/SCOM1PAD1/TC2_2") (pintype "bidirectional"))
      (node (ref "Y1") (pin "P$1") (pinfunction "1_P$1") (pintype "bidirectional"))
    )
    (net (code "37") (name "Net-(IC5-VDDANA)") (class "Default")
      (node (ref "C22") (pin "2") (pinfunction "2_2") (pintype "passive"))
      (node (ref "IC5") (pin "6") (pinfunction "VDDANA_6") (pintype "power_in"))
      (node (ref "L5") (pin "2") (pinfunction "2_2") (pintype "passive"))
    )
    (net (code "38") (name "Net-(IC5-VDDCORE1)") (class "Default")
      (node (ref "C26") (pin "2") (pinfunction "2_2") (pintype "passive"))
      (node (ref "IC5") (pin "43") (pinfunction "VDDCORE1_43") (pintype "input"))
    )
    (net (code "39") (name "Net-(LED1-BLUE)") (class "Default")
      (node (ref "LED1") (pin "2") (pinfunction "BLUE_2") (pintype "passive"))
      (node (ref "R21") (pin "2") (pinfunction "2_2") (pintype "passive"))
    )
    (net (code "40") (name "Net-(LED1-GREEN)") (class "Default")
      (node (ref "LED1") (pin "3") (pinfunction "GREEN_3") (pintype "passive"))
      (node (ref "R20") (pin "2") (pinfunction "2_2") (pintype "passive"))
    )
    (net (code "41") (name "Net-(LED1-RED)") (class "Default")
      (node (ref "LED1") (pin "4") (pinfunction "RED_4") (pintype "passive"))
      (node (ref "R19") (pin "2") (pinfunction "2_2") (pintype "passive"))
    )
    (net (code "42") (name "Net-(LED2-PadK)") (class "Default")
      (node (ref "LED2") (pin "K") (pinfunction "K_K") (pintype "output"))
      (node (ref "R18") (pin "2") (pinfunction "2_2") (pintype "passive"))
    )
    (net (code "43") (name "Net-(LED3-PadK)") (class "Default")
      (node (ref "LED3") (pin "K") (pinfunction "K_K") (pintype "output"))
      (node (ref "R4") (pin "2") (pinfunction "2_2") (pintype "passive"))
    )
    (net (code "44") (name "Net-(Q1A-G)") (class "Default")
      (node (ref "Q1") (pin "2") (pinfunction "G_2") (pintype "passive"))
      (node (ref "Q1") (pin "5") (pinfunction "G_5") (pintype "passive"))
      (node (ref "Q5") (pin "3") (pinfunction "D_3") (pintype "passive"))
      (node (ref "R26") (pin "2") (pinfunction "2_2") (pintype "passive"))
    )
    (net (code "45") (name "Net-(Q1A-S)") (class "Default")
      (node (ref "L1") (pin "1") (pinfunction "1_1") (pintype "passive"))
      (node (ref "Q1") (pin "1") (pinfunction "S_1") (pintype "passive"))
      (node (ref "Q1") (pin "4") (pinfunction "S_4") (pintype "passive"))
      (node (ref "R26") (pin "1") (pinfunction "1_1") (pintype "passive"))
      (node (ref "TVS1") (pin "6") (pinfunction "VBUS_6") (pintype "passive"))
      (node (ref "USB") (pin "P1") (pinfunction "VBUS_P1") (pintype "power_in"))
    )
    (net (code "46") (name "Net-(Q3A-S)") (class "Default")
      (node (ref "C8") (pin "2") (pinfunction "2_2") (pintype "passive"))
      (node (ref "F1") (pin "1") (pinfunction "1_1") (pintype "passive"))
      (node (ref "Q3") (pin "1") (pinfunction "S_1") (pintype "passive"))
      (node (ref "Q3") (pin "4") (pinfunction "S_4") (pintype "passive"))
      (node (ref "R29") (pin "1") (pinfunction "1_1") (pintype "passive"))
    )
    (net (code "47") (name "OTG") (class "Default")
      (node (ref "IC2") (pin "8") (pinfunction "OTG_8") (pintype "bidirectional"))
      (node (ref "IC5") (pin "11") (pinfunction "PA6/EIC/AIN6/SCOM0PAD2/TC1_11") (pintype "bidirectional"))
    )
    (net (code "48") (name "PA30_SWCLK") (class "Default")
      (node (ref "IC5") (pin "45") (pinfunction "PA30/EIC/SCOM1PAD2/TC1_45") (pintype "bidirectional"))
      (node (ref "SWD") (pin "4") (pinfunction "4_4") (pintype "passive"))
    )
    (net (code "49") (name "PA31_SWDIO") (class "Default")
      (node (ref "IC5") (pin "46") (pinfunction "PA31/EIC/SCOM1PAD3/TC1_46") (pintype "bidirectional"))
      (node (ref "SWD") (pin "2") (pinfunction "2_2") (pintype "passive"))
    )
    (net (code "50") (name "PWM_HEATER_CO") (class "Default")
      (node (ref "IC5") (pin "13") (pinfunction "PA8/I2C/AIN16/SCOM2PAD0+/TC0_13") (pintype "bidirectional"))
      (node (ref "IDC") (pin "5") (pinfunction "5_5") (pintype "passive"))
      (node (ref "R24") (pin "1") (pinfunction "1_1") (pintype "passive"))
    )
    (net (code "51") (name "PWM_HEATER_NOX") (class "Default")
      (node (ref "IC5") (pin "14") (pinfunction "PA9/I2C/EIC/AIN17/SCOM2PAD1+/TC0_14") (pintype "bidirectional"))
      (node (ref "IDC") (pin "3") (pinfunction "3_3") (pintype "passive"))
      (node (ref "R25") (pin "1") (pinfunction "1_1") (pintype "passive"))
    )
    (net (code "52") (name "RESET") (class "Default")
      (node (ref "D1") (pin "A") (pinfunction "A_A") (pintype "passive"))
      (node (ref "IC4") (pin "5") (pinfunction "GPIO14_5") (pintype "bidirectional"))
      (node (ref "P2") (pin "3") (pinfunction "2_3") (pintype "passive"))
      (node (ref "P2") (pin "4") (pinfunction "2_4") (pintype "passive"))
      (node (ref "R15") (pin "2") (pinfunction "2_2") (pintype "passive"))
      (node (ref "R16") (pin "1") (pinfunction "1_1") (pintype "passive"))
      (node (ref "SWD") (pin "10") (pinfunction "10_10") (pintype "passive"))
    )
    (net (code "53") (name "RXWIFI") (class "Default")
      (node (ref "IC4") (pin "22") (pinfunction "TXD_22") (pintype "output"))
      (node (ref "IC5") (pin "10") (pinfunction "PA5/EIC/AIN5/SCOM0PAD1/TC0_10") (pintype "bidirectional"))
    )
    (net (code "54") (name "RX_PMS") (class "Default")
      (node (ref "IC5") (pin "48") (pinfunction "PB3/EIC/AIN11/SCOM5PAD1_48") (pintype "bidirectional"))
      (node (ref "IDC") (pin "9") (pinfunction "9_9") (pintype "passive"))
    )
    (net (code "55") (name "SCK") (class "Default")
      (node (ref "IC5") (pin "20") (pinfunction "PB11/EIC/SCOM4PAD3/TC5_20") (pintype "bidirectional"))
      (node (ref "IC6") (pin "6") (pinfunction "SCK_6") (pintype "bidirectional"))
      (node (ref "SD1") (pin "5") (pinfunction "CLK_5") (pintype "bidirectional"))
    )
    (net (code "56") (name "SCL") (class "Default")
      (node (ref "IC1") (pin "A3") (pinfunction "SCL_A3") (pintype "bidirectional"))
      (node (ref "IC2") (pin "5") (pinfunction "SCL_5") (pintype "bidirectional"))
      (node (ref "IC5") (pin "32") (pinfunction "PA23/I2C/EIC/SCOM5PAD1+/TC4_32") (pintype "bidirectional"))
      (node (ref "IDC") (pin "4") (pinfunction "4_4") (pintype "passive"))
      (node (ref "R14") (pin "1") (pinfunction "1_1") (pintype "passive"))
    )
    (net (code "57") (name "SCL_GROOVE") (class "Default")
      (node (ref "IC5") (pin "26") (pinfunction "PA17/I2C/EIC/SCOM1PAD1+/TC2_26") (pintype "bidirectional"))
      (node (ref "R22") (pin "1") (pinfunction "1_1") (pintype "passive"))
      (node (ref "X1") (pin "1") (pinfunction "1_1") (pintype "bidirectional"))
    )
    (net (code "58") (name "SDA") (class "Default")
      (node (ref "IC1") (pin "A2") (pinfunction "SDA_A2") (pintype "bidirectional"))
      (node (ref "IC2") (pin "6") (pinfunction "SDA_6") (pintype "bidirectional"))
      (node (ref "IC5") (pin "31") (pinfunction "PA22/I2C/EIC/SCOM5PAD0+/TC4_31") (pintype "bidirectional"))
      (node (ref "IDC") (pin "6") (pinfunction "6_6") (pintype "passive"))
      (node (ref "R13") (pin "1") (pinfunction "1_1") (pintype "passive"))
    )
    (net (code "59") (name "SDA_GROOVE") (class "Default")
      (node (ref "IC5") (pin "25") (pinfunction "PA16/I2C/EIC/SCOM1PAD0+/TC2_25") (pintype "bidirectional"))
      (node (ref "R23") (pin "1") (pinfunction "1_1") (pintype "passive"))
      (node (ref "X1") (pin "2") (pinfunction "2_2") (pintype "bidirectional"))
    )
    (net (code "60") (name "SW_GROOVE") (class "Default")
      (node (ref "IC5") (pin "38") (pinfunction "PB23/EIC/SCOM5PAD3_38") (pintype "bidirectional"))
      (node (ref "Q3") (pin "2") (pinfunction "G_2") (pintype "passive"))
      (node (ref "Q3") (pin "5") (pinfunction "G_5") (pintype "passive"))
      (node (ref "R29") (pin "2") (pinfunction "2_2") (pintype "passive"))
    )
    (net (code "61") (name "SW_PMS") (class "Default")
      (node (ref "IC5") (pin "41") (pinfunction "PA28/EIC_41") (pintype "bidirectional"))
      (node (ref "Q5") (pin "1") (pinfunction "G_1") (pintype "passive"))
      (node (ref "R27") (pin "2") (pinfunction "2_2") (pintype "passive"))
    )
    (net (code "62") (name "SW_WIFI") (class "Default")
      (node (ref "IC5") (pin "37") (pinfunction "PB22/EIC/SCOM5PAD2_37") (pintype "bidirectional"))
      (node (ref "Q4") (pin "2") (pinfunction "G_2") (pintype "passive"))
      (node (ref "Q4") (pin "5") (pinfunction "G_5") (pintype "passive"))
      (node (ref "R28") (pin "1") (pinfunction "1_1") (pintype "passive"))
    )
    (net (code "63") (name "TARGET_RESET") (class "Default")
      (node (ref "C3") (pin "2") (pinfunction "2_2") (pintype "passive"))
      (node (ref "IC5") (pin "40") (pinfunction "RESETN_40") (pintype "bidirectional"))
      (node (ref "R15") (pin "1") (pinfunction "1_1") (pintype "passive"))
    )
    (net (code "64") (name "TARGET_USB_N") (class "Default")
      (node (ref "IC5") (pin "33") (pinfunction "PA24/EIC/SCOM3PAD2+/TC5_33") (pintype "bidirectional"))
      (node (ref "TVS1") (pin "2") (pinfunction "D-_2") (pintype "passive"))
      (node (ref "USB") (pin "P2") (pinfunction "D-_P2") (pintype "bidirectional"))
    )
    (net (code "65") (name "TARGET_USB_P") (class "Default")
      (node (ref "IC5") (pin "34") (pinfunction "PA25/EIC/SCOM3PAD3+/TC5_34") (pintype "bidirectional"))
      (node (ref "TVS1") (pin "1") (pinfunction "D+_1") (pintype "passive"))
      (node (ref "USB") (pin "P3") (pinfunction "D+_P3") (pintype "bidirectional"))
    )
    (net (code "66") (name "TXLED") (class "Default")
      (node (ref "IC5") (pin "39") (pinfunction "PA27/EIC_39") (pintype "bidirectional"))
      (node (ref "R18") (pin "1") (pinfunction "1_1") (pintype "passive"))
    )
    (net (code "67") (name "TXWIFI") (class "Default")
      (node (ref "IC4") (pin "21") (pinfunction "RXD_21") (pintype "input"))
      (node (ref "IC5") (pin "9") (pinfunction "PA4/EIC/REF/AIN4/SCOM0PAD0/TC0_9") (pintype "bidirectional"))
    )
    (net (code "68") (name "TX_PMS") (class "Default")
      (node (ref "IC5") (pin "47") (pinfunction "PB2/EIC/AIN10/SCOM5PAD0_47") (pintype "bidirectional"))
      (node (ref "IDC") (pin "11") (pinfunction "11_11") (pintype "passive"))
    )
    (net (code "69") (name "USB_ID") (class "Default")
      (node (ref "Q2") (pin "2") (pinfunction "G_2") (pintype "passive"))
      (node (ref "R7") (pin "1") (pinfunction "1_1") (pintype "passive"))
      (node (ref "TVS1") (pin "3") (pinfunction "ID_3") (pintype "passive"))
      (node (ref "USB") (pin "P4") (pinfunction "ID_P4") (pintype "bidirectional"))
    )
    (net (code "70") (name "V+") (class "Default")
      (node (ref "L3") (pin "2") (pinfunction "2_2") (pintype "passive"))
      (node (ref "Q4") (pin "3") (pinfunction "D_3") (pintype "passive"))
      (node (ref "Q4") (pin "6") (pinfunction "D_6") (pintype "passive"))
      (node (ref "Q4") (pin "TP1") (pinfunction "D_TP1") (pintype "passive"))
      (node (ref "Q4") (pin "TP2") (pinfunction "D_TP2") (pintype "passive"))
    )
    (net (code "71") (name "VBAT") (class "Default")
      (node (ref "BAT") (pin "2") (pinfunction "2_2") (pintype "passive"))
      (node (ref "C21") (pin "2") (pinfunction "2_2") (pintype "passive"))
      (node (ref "IC1") (pin "C1") (pinfunction "SRP_C1") (pintype "bidirectional"))
      (node (ref "IC1") (pin "C3") (pinfunction "BAT_C3") (pintype "bidirectional"))
      (node (ref "R2") (pin "2") (pinfunction "2_2") (pintype "passive"))
    )
    (net (code "72") (name "VBAT'") (class "Default")
      (node (ref "IC1") (pin "C2") (pinfunction "SRN_C2") (pintype "bidirectional"))
      (node (ref "IC2") (pin "13") (pinfunction "VBAT_13") (pintype "bidirectional"))
      (node (ref "IC2") (pin "14") (pinfunction "VBAT_14") (pintype "bidirectional"))
      (node (ref "R2") (pin "1") (pinfunction "1_1") (pintype "passive"))
    )
    (net (code "73") (name "VCC") (class "Default")
      (node (ref "C2") (pin "2") (pinfunction "2_2") (pintype "passive"))
      (node (ref "C23") (pin "2") (pinfunction "2_2") (pintype "passive"))
      (node (ref "C24") (pin "2") (pinfunction "2_2") (pintype "passive"))
      (node (ref "C25") (pin "2") (pinfunction "2_2") (pintype "passive"))
      (node (ref "C9") (pin "2") (pinfunction "2_2") (pintype "passive"))
      (node (ref "D1") (pin "C") (pinfunction "C_C") (pintype "passive"))
      (node (ref "F1") (pin "2") (pinfunction "2_2") (pintype "passive"))
      (node (ref "F2") (pin "1") (pinfunction "1_1") (pintype "passive"))
      (node (ref "IC5") (pin "17") (pinfunction "VDDIO1_17") (pintype "power_in"))
      (node (ref "IC5") (pin "36") (pinfunction "VDDIO2_36") (pintype "power_in"))
      (node (ref "IC5") (pin "44") (pinfunction "VDDIN_44") (pintype "power_in"))
      (node (ref "IC6") (pin "8") (pinfunction "VCC_8") (pintype "bidirectional"))
      (node (ref "IDC") (pin "1") (pinfunction "1_1") (pintype "passive"))
      (node (ref "IDC") (pin "2") (pinfunction "2_2") (pintype "passive"))
      (node (ref "L5") (pin "1") (pinfunction "1_1") (pintype "passive"))
      (node (ref "LED1") (pin "1") (pinfunction "A_1") (pintype "passive"))
      (node (ref "LED2") (pin "A") (pinfunction "A_A") (pintype "input"))
      (node (ref "LED3") (pin "A") (pinfunction "A_A") (pintype "input"))
      (node (ref "Q4") (pin "1") (pinfunction "S_1") (pintype "passive"))
      (node (ref "Q4") (pin "4") (pinfunction "S_4") (pintype "passive"))
      (node (ref "R13") (pin "2") (pinfunction "2_2") (pintype "passive"))
      (node (ref "R14") (pin "2") (pinfunction "2_2") (pintype "passive"))
      (node (ref "R16") (pin "2") (pinfunction "2_2") (pintype "passive"))
      (node (ref "R17") (pin "2") (pinfunction "2_2") (pintype "passive"))
      (node (ref "R24") (pin "2") (pinfunction "2_2") (pintype "passive"))
      (node (ref "R25") (pin "2") (pinfunction "2_2") (pintype "passive"))
      (node (ref "R28") (pin "2") (pinfunction "2_2") (pintype "passive"))
      (node (ref "SD1") (pin "4") (pinfunction "VCC_4") (pintype "bidirectional"))
      (node (ref "SWD") (pin "1") (pinfunction "1_1") (pintype "passive"))
    )
    (net (code "74") (name "VCC_GROOVE") (class "Default")
      (node (ref "Q3") (pin "3") (pinfunction "D_3") (pintype "passive"))
      (node (ref "Q3") (pin "6") (pinfunction "D_6") (pintype "passive"))
      (node (ref "Q3") (pin "TP1") (pinfunction "D_TP1") (pintype "passive"))
      (node (ref "Q3") (pin "TP2") (pinfunction "D_TP2") (pintype "passive"))
      (node (ref "R22") (pin "2") (pinfunction "2_2") (pintype "passive"))
      (node (ref "R23") (pin "2") (pinfunction "2_2") (pintype "passive"))
      (node (ref "X1") (pin "3") (pinfunction "3_3") (pintype "bidirectional"))
    )
    (net (code "75") (name "VSYS") (class "Default")
      (node (ref "C10") (pin "2") (pinfunction "2_2") (pintype "passive"))
      (node (ref "C11") (pin "2") (pinfunction "2_2") (pintype "passive"))
      (node (ref "C15") (pin "2") (pinfunction "2_2") (pintype "passive"))
      (node (ref "C16") (pin "2") (pinfunction "2_2") (pintype "passive"))
      (node (ref "IC2") (pin "15") (pinfunction "SYS_15") (pintype "bidirectional"))
      (node (ref "IC2") (pin "16") (pinfunction "SYS_16") (pintype "bidirectional"))
      (node (ref "IC3") (pin "6") (pinfunction "IN_6") (pintype "bidirectional"))
      (node (ref "L2") (pin "2") (pinfunction "2_2") (pintype "bidirectional"))
      (node (ref "R5") (pin "1") (pinfunction "1_1") (pintype "passive"))
    )
    (net (code "76") (name "VUSB") (class "Default")
      (node (ref "C4") (pin "2") (pinfunction "2_2") (pintype "passive"))
      (node (ref "C5") (pin "2") (pinfunction "2_2") (pintype "passive"))
      (node (ref "C6") (pin "2") (pinfunction "2_2") (pintype "passive"))
      (node (ref "IC2") (pin "1") (pinfunction "VBUS_1") (pintype "bidirectional"))
      (node (ref "IC2") (pin "24") (pinfunction "VBUS_24") (pintype "bidirectional"))
      (node (ref "L1") (pin "2") (pinfunction "2_2") (pintype "passive"))
      (node (ref "R7") (pin "2") (pinfunction "2_2") (pintype "passive"))
      (node (ref "R8") (pin "2") (pinfunction "2_2") (pintype "passive"))
    )
    (net (code "77") (name "WIFI_LED") (class "Default")
      (node (ref "IC4") (pin "19") (pinfunction "GPIO5_19") (pintype "bidirectional"))
      (node (ref "R4") (pin "1") (pinfunction "1_1") (pintype "passive"))
    )
    (net (code "78") (name "unconnected-(IC2-QON-Pad12)") (class "Default")
      (node (ref "IC2") (pin "12") (pinfunction "QON_12") (pintype "bidirectional"))
    )
    (net (code "79") (name "unconnected-(IC2-STAT-Pad4)") (class "Default")
      (node (ref "IC2") (pin "4") (pinfunction "STAT_4") (pintype "bidirectional"))
    )
    (net (code "80") (name "unconnected-(IC2-{slash}PG-Pad3)") (class "Default")
      (node (ref "IC2") (pin "3") (pinfunction "/PG_3") (pintype "bidirectional"))
    )
    (net (code "81") (name "unconnected-(IC3-PG-Pad4)") (class "Default")
      (node (ref "IC3") (pin "4") (pinfunction "PG_4") (pintype "bidirectional"))
    )
    (net (code "82") (name "unconnected-(IC4-ADC-Pad2)") (class "Default")
      (node (ref "IC4") (pin "2") (pinfunction "ADC_2") (pintype "passive"))
    )
    (net (code "83") (name "unconnected-(IC4-GPIO9-Pad11)") (class "Default")
      (node (ref "IC4") (pin "11") (pinfunction "GPIO9_11") (pintype "bidirectional"))
    )
    (net (code "84") (name "unconnected-(IC4-GPIO10-Pad12)") (class "Default")
      (node (ref "IC4") (pin "12") (pinfunction "GPIO10_12") (pintype "bidirectional"))
    )
    (net (code "85") (name "unconnected-(IC4-GPIO12-Pad6)") (class "Default")
      (node (ref "IC4") (pin "6") (pinfunction "GPIO12_6") (pintype "bidirectional"))
    )
    (net (code "86") (name "unconnected-(IC4-GPIO13-Pad7)") (class "Default")
      (node (ref "IC4") (pin "7") (pinfunction "GPIO13_7") (pintype "bidirectional"))
    )
    (net (code "87") (name "unconnected-(IC4-GPIO16-Pad4)") (class "Default")
      (node (ref "IC4") (pin "4") (pinfunction "GPIO16_4") (pintype "bidirectional"))
    )
    (net (code "88") (name "unconnected-(IC4-MISO-Pad10)") (class "Default")
      (node (ref "IC4") (pin "10") (pinfunction "MISO_10") (pintype "passive"))
    )
    (net (code "89") (name "unconnected-(IC4-MOSI-Pad13)") (class "Default")
      (node (ref "IC4") (pin "13") (pinfunction "MOSI_13") (pintype "bidirectional"))
    )
    (net (code "90") (name "unconnected-(IC4-SCLK-Pad14)") (class "Default")
      (node (ref "IC4") (pin "14") (pinfunction "SCLK_14") (pintype "bidirectional"))
    )
    (net (code "91") (name "unconnected-(IC6-IO3{slash}RESET#-Pad7)") (class "Default")
      (node (ref "IC6") (pin "7") (pinfunction "IO3/RESET#_7") (pintype "bidirectional"))
    )
    (net (code "92") (name "unconnected-(IC6-WP#{slash}IO2-Pad3)") (class "Default")
      (node (ref "IC6") (pin "3") (pinfunction "WP#/IO2_3") (pintype "bidirectional"))
    )
    (net (code "93") (name "unconnected-(SD1-DAT1-Pad8)") (class "Default")
      (node (ref "SD1") (pin "8") (pinfunction "DAT1_8") (pintype "bidirectional"))
    )
    (net (code "94") (name "unconnected-(SD1-DAT2-Pad1)") (class "Default")
      (node (ref "SD1") (pin "1") (pinfunction "DAT2_1") (pintype "bidirectional"))
    )
    (net (code "95") (name "unconnected-(SWD-Pad6)") (class "Default")
      (node (ref "SWD") (pin "6") (pinfunction "6_6") (pintype "passive"))
    )
    (net (code "96") (name "unconnected-(SWD-Pad7)") (class "Default")
      (node (ref "SWD") (pin "7") (pinfunction "7_7") (pintype "passive"))
    )
    (net (code "97") (name "unconnected-(SWD-Pad8)") (class "Default")
      (node (ref "SWD") (pin "8") (pinfunction "8_8") (pintype "passive"))
    )
    (net (code "98") (name "unconnected-(TVS1-N.C.-Pad5)") (class "Default")
      (node (ref "TVS1") (pin "5") (pinfunction "N.C._5") (pintype "passive"))
    )
  )
)
